# PULSE_MUX.net
KiCad netlist of a schematic drawn in Altium Designer
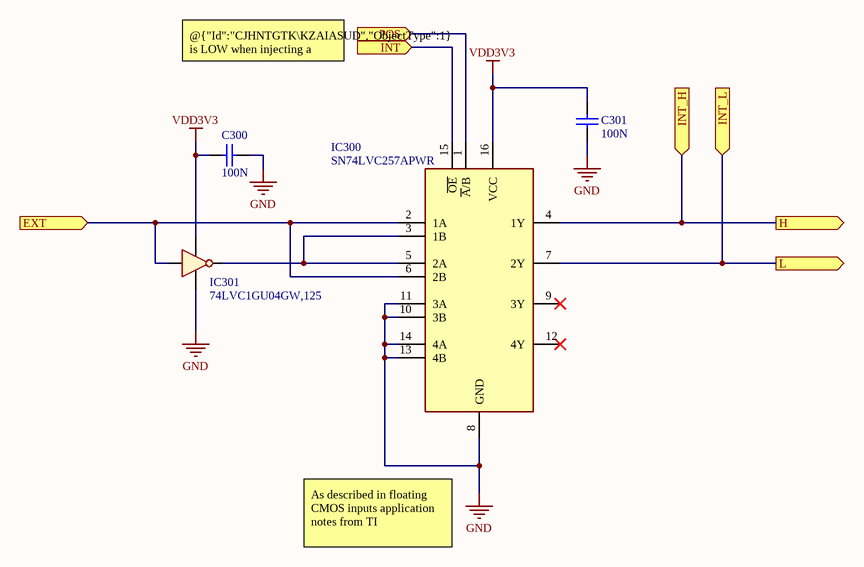
[diagram p0: PULSE_MUX.SchDoc]

(export (version "E")
  (design (tool "Eeschema 10.0.6"))
  (components
    (comp (ref "C300")
      (value "Cap")
      (footprint "CAPC0603N")
      (fields
        (field (name "VALUE_4C") "100N")
        (field (name "VOLTAGE") "25V")
        (field (name "TOLERANCE") "0.1")
      )
      (libsource (lib "Capacitors") (part "Cap"))
    )
    (comp (ref "C301")
      (value "Cap")
      (footprint "CAPC0603N")
      (fields
        (field (name "VALUE_4C") "100N")
        (field (name "VOLTAGE") "25V")
        (field (name "TOLERANCE") "0.1")
      )
      (libsource (lib "Capacitors") (part "Cap"))
    )
    (comp (ref "IC300")
      (value "SN74LVC257APWR")
      (footprint "SOP65P640X120-16N")
      (libsource (lib "Integrated_circuits") (part "SN74LVC257APWR"))
    )
    (comp (ref "IC301")
      (value "INV_SINGLE")
      (footprint "SOT65P212X110-5N")
      (fields (field (name "MANUFCODE") "74LVC1GU04GW,125"))
      (libsource (lib "Integrated_circuits") (part "INV_SINGLE"))
    )
  )
  (nets
    (net (code "1") (name "/EXT") (class "Default")
      (node (ref "IC300") (pin "2") (pinfunction "1A_2") (pintype "passive"))
      (node (ref "IC300") (pin "6") (pinfunction "2B_6") (pintype "passive"))
      (node (ref "IC301") (pin "2") (pinfunction "A_2") (pintype "passive"))
    )
    (net (code "2") (name "/H") (class "Default")
      (node (ref "IC300") (pin "4") (pinfunction "1Y_4") (pintype "passive"))
    )
    (net (code "3") (name "/INT") (class "Default")
      (node (ref "IC300") (pin "15") (pinfunction "~{OE}_15") (pintype "passive"))
    )
    (net (code "4") (name "/INT_L") (class "Default")
      (node (ref "IC300") (pin "7") (pinfunction "2Y_7") (pintype "passive"))
    )
    (net (code "5") (name "/POS") (class "Default")
      (node (ref "IC300") (pin "1") (pinfunction "~{A}/B_1") (pintype "passive"))
    )
    (net (code "6") (name "GND") (class "Default")
      (node (ref "C300") (pin "1") (pinfunction "1_1") (pintype "passive"))
      (node (ref "C301") (pin "1") (pinfunction "1_1") (pintype "passive"))
      (node (ref "IC300") (pin "10") (pinfunction "3B_10") (pintype "passive"))
      (node (ref "IC300") (pin "11") (pinfunction "3A_11") (pintype "passive"))
      (node (ref "IC300") (pin "13") (pinfunction "4B_13") (pintype "passive"))
      (node (ref "IC300") (pin "14") (pinfunction "4A_14") (pintype "passive"))
      (node (ref "IC300") (pin "8") (pinfunction "GND_8") (pintype "passive"))
      (node (ref "IC301") (pin "3") (pinfunction "GND_3") (pintype "passive"))
    )
    (net (code "7") (name "Net-(IC300-1B)") (class "Default")
      (node (ref "IC300") (pin "3") (pinfunction "1B_3") (pintype "passive"))
      (node (ref "IC300") (pin "5") (pinfunction "2A_5") (pintype "passive"))
      (node (ref "IC301") (pin "4") (pinfunction "Y_4") (pintype "passive"))
    )
    (net (code "8") (name "VDD3V3") (class "Default")
      (node (ref "C300") (pin "2") (pinfunction "2_2") (pintype "passive"))
      (node (ref "C301") (pin "2") (pinfunction "2_2") (pintype "passive"))
      (node (ref "IC300") (pin "16") (pinfunction "VCC_16") (pintype "passive"))
      (node (ref "IC301") (pin "5") (pinfunction "GND_5") (pintype "passive"))
    )
    (net (code "9") (name "unconnected-(IC300-3Y-Pad9)") (class "Default")
      (node (ref "IC300") (pin "9") (pinfunction "3Y_9") (pintype "passive+no_connect"))
    )
    (net (code "10") (name "unconnected-(IC300-4Y-Pad12)") (class "Default")
      (node (ref "IC300") (pin "12") (pinfunction "4Y_12") (pintype "passive+no_connect"))
    )
  )
)
